# noodle.net
KiCad netlist of a schematic drawn in EAGLE
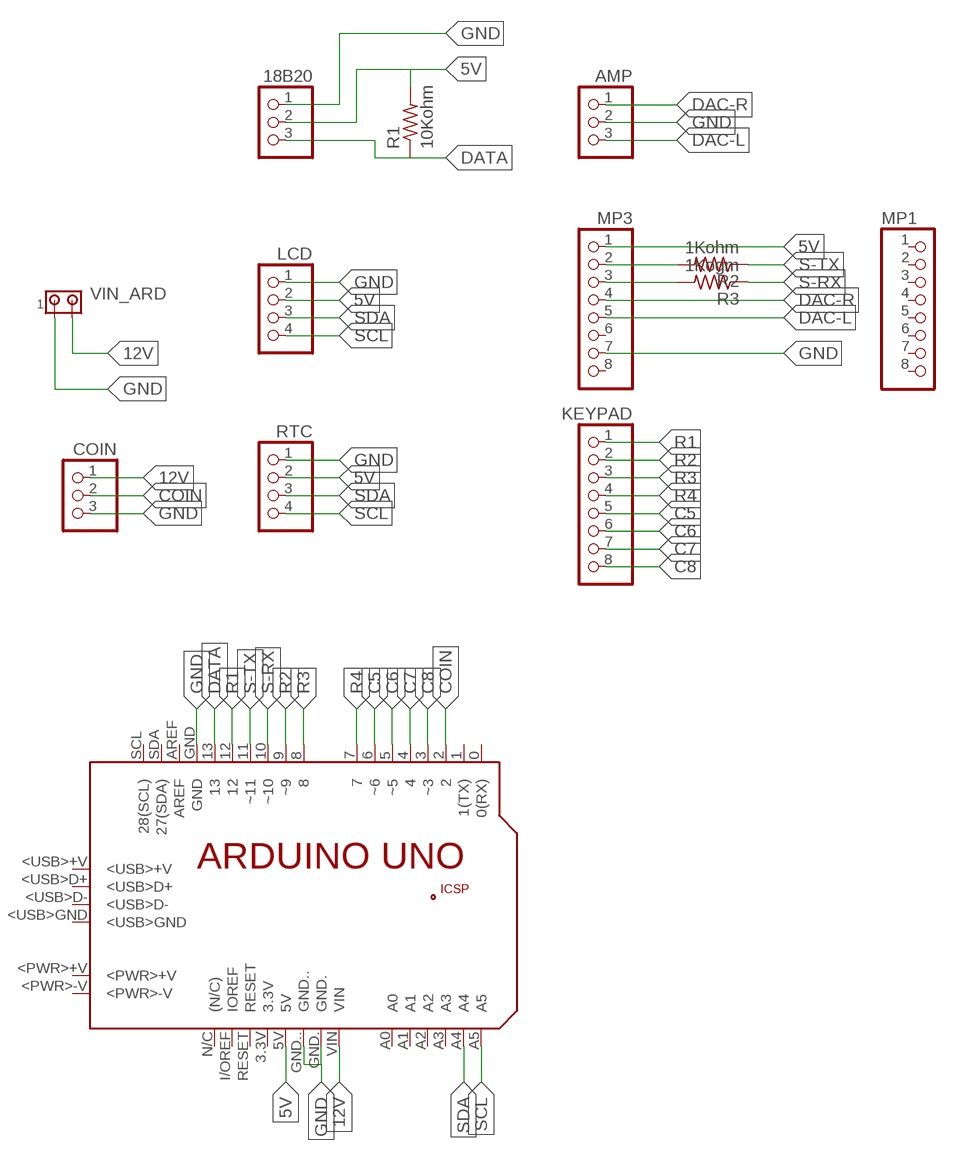
[diagram p0: schematic, sheet 1]

(export (version "E")
  (design (tool "Eeschema 10.0.6"))
  (components
    (comp (ref "18B20")
      (value "PINHD-1X3")
      (footprint "eagle-import:1X03")
      (libsource (lib "eagle-import") (part "PINHD-1X3"))
    )
    (comp (ref "AMP")
      (value "PINHD-1X3")
      (footprint "eagle-import:1X03")
      (libsource (lib "eagle-import") (part "PINHD-1X3"))
    )
    (comp (ref "COIN")
      (value "PINHD-1X3")
      (footprint "eagle-import:1X03")
      (libsource (lib "eagle-import") (part "PINHD-1X3"))
    )
    (comp (ref "KEYPAD")
      (value "PINHD-1X8")
      (footprint "eagle-import:1X08")
      (libsource (lib "eagle-import") (part "PINHD-1X8"))
    )
    (comp (ref "LCD")
      (value "PINHD-1X4")
      (footprint "eagle-import:1X04")
      (libsource (lib "eagle-import") (part "PINHD-1X4"))
    )
    (comp (ref "MP1")
      (value "PINHD-1X8")
      (footprint "eagle-import:1X08")
      (libsource (lib "eagle-import") (part "PINHD-1X8"))
    )
    (comp (ref "MP3")
      (value "PINHD-1X8")
      (footprint "eagle-import:1X08")
      (libsource (lib "eagle-import") (part "PINHD-1X8"))
    )
    (comp (ref "PCB1")
      (value "ARDUINO_UNO")
      (footprint "eagle-import:ARDUINO_UNO")
      (libsource (lib "eagle-import") (part "ARDUINO_UNO"))
    )
    (comp (ref "R1")
      (value "10Kohm")
      (footprint "eagle-import:0207_10")
      (libsource (lib "eagle-import") (part "R-US_0207/10"))
    )
    (comp (ref "R2")
      (value "1Kohm")
      (footprint "eagle-import:0207_10")
      (libsource (lib "eagle-import") (part "R-US_0207/10"))
    )
    (comp (ref "R3")
      (value "1Kogm")
      (footprint "eagle-import:0207_10")
      (libsource (lib "eagle-import") (part "R-US_0207/10"))
    )
    (comp (ref "RTC")
      (value "PINHD-1X4")
      (footprint "eagle-import:1X04")
      (libsource (lib "eagle-import") (part "PINHD-1X4"))
    )
    (comp (ref "VIN_ARD")
      (value "MTA02-156")
      (footprint "eagle-import:1X2MTA")
      (libsource (lib "eagle-import") (part "MTA02-156"))
    )
  )
  (nets
    (net (code "1") (name "5V") (class "Default")
      (node (ref "18B20") (pin "2") (pinfunction "2_2") (pintype "passive"))
      (node (ref "LCD") (pin "2") (pinfunction "2_2") (pintype "passive"))
      (node (ref "MP3") (pin "1") (pinfunction "1_1") (pintype "passive"))
      (node (ref "PCB1") (pin "5V") (pinfunction "5V_5V") (pintype "bidirectional"))
      (node (ref "R1") (pin "2") (pinfunction "2_2") (pintype "passive"))
      (node (ref "RTC") (pin "2") (pinfunction "2_2") (pintype "passive"))
    )
    (net (code "2") (name "12V") (class "Default")
      (node (ref "COIN") (pin "1") (pinfunction "1_1") (pintype "passive"))
      (node (ref "PCB1") (pin "VIN") (pinfunction "VIN_VIN") (pintype "bidirectional"))
      (node (ref "VIN_ARD") (pin "2") (pinfunction "2_2") (pintype "passive"))
    )
    (net (code "3") (name "C5") (class "Default")
      (node (ref "KEYPAD") (pin "5") (pinfunction "5_5") (pintype "passive"))
      (node (ref "PCB1") (pin "6") (pinfunction "~{6}_6") (pintype "bidirectional"))
    )
    (net (code "4") (name "C6") (class "Default")
      (node (ref "KEYPAD") (pin "6") (pinfunction "6_6") (pintype "passive"))
      (node (ref "PCB1") (pin "5") (pinfunction "~{5}_5") (pintype "bidirectional"))
    )
    (net (code "5") (name "C7") (class "Default")
      (node (ref "KEYPAD") (pin "7") (pinfunction "7_7") (pintype "passive"))
      (node (ref "PCB1") (pin "4") (pinfunction "4_4") (pintype "bidirectional"))
    )
    (net (code "6") (name "C8") (class "Default")
      (node (ref "KEYPAD") (pin "8") (pinfunction "8_8") (pintype "passive"))
      (node (ref "PCB1") (pin "3") (pinfunction "~{3}_3") (pintype "bidirectional"))
    )
    (net (code "7") (name "COIN") (class "Default")
      (node (ref "COIN") (pin "2") (pinfunction "2_2") (pintype "passive"))
      (node (ref "PCB1") (pin "2") (pinfunction "2_2") (pintype "bidirectional"))
    )
    (net (code "8") (name "DAC-L") (class "Default")
      (node (ref "AMP") (pin "3") (pinfunction "3_3") (pintype "passive"))
      (node (ref "MP3") (pin "5") (pinfunction "5_5") (pintype "passive"))
    )
    (net (code "9") (name "DAC-R") (class "Default")
      (node (ref "AMP") (pin "1") (pinfunction "1_1") (pintype "passive"))
      (node (ref "MP3") (pin "4") (pinfunction "4_4") (pintype "passive"))
    )
    (net (code "10") (name "DATA") (class "Default")
      (node (ref "18B20") (pin "3") (pinfunction "3_3") (pintype "passive"))
      (node (ref "PCB1") (pin "13") (pinfunction "13_13") (pintype "bidirectional"))
      (node (ref "R1") (pin "1") (pinfunction "1_1") (pintype "passive"))
    )
    (net (code "11") (name "GND") (class "Default")
      (node (ref "18B20") (pin "1") (pinfunction "1_1") (pintype "passive"))
      (node (ref "AMP") (pin "2") (pinfunction "2_2") (pintype "passive"))
      (node (ref "COIN") (pin "3") (pinfunction "3_3") (pintype "passive"))
      (node (ref "LCD") (pin "1") (pinfunction "1_1") (pintype "passive"))
      (node (ref "MP3") (pin "7") (pinfunction "7_7") (pintype "passive"))
      (node (ref "PCB1") (pin "GND") (pinfunction "GND_GND") (pintype "bidirectional"))
      (node (ref "PCB1") (pin "GND.") (pinfunction "GND._GND.") (pintype "bidirectional"))
      (node (ref "PCB1") (pin "GND..") (pinfunction "GND.._GND..") (pintype "bidirectional"))
      (node (ref "RTC") (pin "1") (pinfunction "1_1") (pintype "passive"))
      (node (ref "VIN_ARD") (pin "1") (pinfunction "1_1") (pintype "passive"))
    )
    (net (code "12") (name "Net-(MP3-Pad2)") (class "Default")
      (node (ref "MP3") (pin "2") (pinfunction "2_2") (pintype "passive"))
      (node (ref "R2") (pin "2") (pinfunction "2_2") (pintype "passive"))
    )
    (net (code "13") (name "Net-(MP3-Pad3)") (class "Default")
      (node (ref "MP3") (pin "3") (pinfunction "3_3") (pintype "passive"))
      (node (ref "R3") (pin "2") (pinfunction "2_2") (pintype "passive"))
    )
    (net (code "14") (name "R1") (class "Default")
      (node (ref "KEYPAD") (pin "1") (pinfunction "1_1") (pintype "passive"))
      (node (ref "PCB1") (pin "12") (pinfunction "12_12") (pintype "bidirectional"))
    )
    (net (code "15") (name "R2") (class "Default")
      (node (ref "KEYPAD") (pin "2") (pinfunction "2_2") (pintype "passive"))
      (node (ref "PCB1") (pin "9") (pinfunction "~{9}_9") (pintype "bidirectional"))
    )
    (net (code "16") (name "R3") (class "Default")
      (node (ref "KEYPAD") (pin "3") (pinfunction "3_3") (pintype "passive"))
      (node (ref "PCB1") (pin "8") (pinfunction "8_8") (pintype "bidirectional"))
    )
    (net (code "17") (name "R4") (class "Default")
      (node (ref "KEYPAD") (pin "4") (pinfunction "4_4") (pintype "passive"))
      (node (ref "PCB1") (pin "7") (pinfunction "7_7") (pintype "bidirectional"))
    )
    (net (code "18") (name "S-RX") (class "Default")
      (node (ref "PCB1") (pin "10") (pinfunction "~{10}_10") (pintype "bidirectional"))
      (node (ref "R3") (pin "1") (pinfunction "1_1") (pintype "passive"))
    )
    (net (code "19") (name "S-TX") (class "Default")
      (node (ref "PCB1") (pin "11") (pinfunction "~{11}_11") (pintype "bidirectional"))
      (node (ref "R2") (pin "1") (pinfunction "1_1") (pintype "passive"))
    )
    (net (code "20") (name "SCL") (class "Default")
      (node (ref "LCD") (pin "4") (pinfunction "4_4") (pintype "passive"))
      (node (ref "PCB1") (pin "A5") (pinfunction "A5_A5") (pintype "bidirectional"))
      (node (ref "RTC") (pin "4") (pinfunction "4_4") (pintype "passive"))
    )
    (net (code "21") (name "SDA") (class "Default")
      (node (ref "LCD") (pin "3") (pinfunction "3_3") (pintype "passive"))
      (node (ref "PCB1") (pin "A4") (pinfunction "A4_A4") (pintype "bidirectional"))
      (node (ref "RTC") (pin "3") (pinfunction "3_3") (pintype "passive"))
    )
    (net (code "22") (name "unconnected-(MP1-Pad1)") (class "Default")
      (node (ref "MP1") (pin "1") (pinfunction "1_1") (pintype "passive"))
    )
    (net (code "23") (name "unconnected-(MP1-Pad2)") (class "Default")
      (node (ref "MP1") (pin "2") (pinfunction "2_2") (pintype "passive"))
    )
    (net (code "24") (name "unconnected-(MP1-Pad3)") (class "Default")
      (node (ref "MP1") (pin "3") (pinfunction "3_3") (pintype "passive"))
    )
    (net (code "25") (name "unconnected-(MP1-Pad4)") (class "Default")
      (node (ref "MP1") (pin "4") (pinfunction "4_4") (pintype "passive"))
    )
    (net (code "26") (name "unconnected-(MP1-Pad5)") (class "Default")
      (node (ref "MP1") (pin "5") (pinfunction "5_5") (pintype "passive"))
    )
    (net (code "27") (name "unconnected-(MP1-Pad6)") (class "Default")
      (node (ref "MP1") (pin "6") (pinfunction "6_6") (pintype "passive"))
    )
    (net (code "28") (name "unconnected-(MP1-Pad7)") (class "Default")
      (node (ref "MP1") (pin "7") (pinfunction "7_7") (pintype "passive"))
    )
    (net (code "29") (name "unconnected-(MP1-Pad8)") (class "Default")
      (node (ref "MP1") (pin "8") (pinfunction "8_8") (pintype "passive"))
    )
    (net (code "30") (name "unconnected-(MP3-Pad6)") (class "Default")
      (node (ref "MP3") (pin "6") (pinfunction "6_6") (pintype "passive"))
    )
    (net (code "31") (name "unconnected-(MP3-Pad8)") (class "Default")
      (node (ref "MP3") (pin "8") (pinfunction "8_8") (pintype "passive"))
    )
    (net (code "32") (name "unconnected-(PCB1-(N{slash}C)-PadN{slash}C)") (class "Default")
      (node (ref "PCB1") (pin "N/C") (pinfunction "(N/C)_N/C") (pintype "bidirectional"))
    )
    (net (code "33") (name "unconnected-(PCB1-0(RX)-Pad0)") (class "Default")
      (node (ref "PCB1") (pin "0") (pinfunction "0(RX)_0") (pintype "bidirectional"))
    )
    (net (code "34") (name "unconnected-(PCB1-1(TX)-Pad1)") (class "Default")
      (node (ref "PCB1") (pin "1") (pinfunction "1(TX)_1") (pintype "bidirectional"))
    )
    (net (code "35") (name "unconnected-(PCB1-27(SDA)-PadSDA)") (class "Default")
      (node (ref "PCB1") (pin "SDA") (pinfunction "27(SDA)_SDA") (pintype "bidirectional"))
    )
    (net (code "36") (name "unconnected-(PCB1-28(SCL)-PadSCL)") (class "Default")
      (node (ref "PCB1") (pin "SCL") (pinfunction "28(SCL)_SCL") (pintype "bidirectional"))
    )
    (net (code "37") (name "unconnected-(PCB1-IOREF-PadI{slash}OREF)") (class "Default")
      (node (ref "PCB1") (pin "I/OREF") (pinfunction "IOREF_I/OREF") (pintype "bidirectional"))
    )
    (net (code "38") (name "unconnected-(PCB1-Pad+5V)") (class "Default")
      (node (ref "PCB1") (pin "+5V") (pinfunction "+5V_+5V") (pintype "bidirectional"))
    )
    (net (code "39") (name "unconnected-(PCB1-Pad3.3V)") (class "Default")
      (node (ref "PCB1") (pin "3.3V") (pinfunction "3.3V_3.3V") (pintype "bidirectional"))
    )
    (net (code "40") (name "unconnected-(PCB1-Pad<PWR>+V)") (class "Default")
      (node (ref "PCB1") (pin "<PWR>+V") (pinfunction "<PWR>+V_<PWR>+V") (pintype "bidirectional"))
    )
    (net (code "41") (name "unconnected-(PCB1-Pad<PWR>-V)") (class "Default")
      (node (ref "PCB1") (pin "<PWR>-V") (pinfunction "<PWR>-V_<PWR>-V") (pintype "bidirectional"))
    )
    (net (code "42") (name "unconnected-(PCB1-Pad<USB>+V)") (class "Default")
      (node (ref "PCB1") (pin "<USB>+V") (pinfunction "<USB>+V_<USB>+V") (pintype "bidirectional"))
    )
    (net (code "43") (name "unconnected-(PCB1-Pad<USB>D+)") (class "Default")
      (node (ref "PCB1") (pin "<USB>D+") (pinfunction "<USB>D+_<USB>D+") (pintype "bidirectional"))
    )
    (net (code "44") (name "unconnected-(PCB1-Pad<USB>D-)") (class "Default")
      (node (ref "PCB1") (pin "<USB>D-") (pinfunction "<USB>D-_<USB>D-") (pintype "bidirectional"))
    )
    (net (code "45") (name "unconnected-(PCB1-Pad<USB>GND)") (class "Default")
      (node (ref "PCB1") (pin "<USB>GND") (pinfunction "<USB>GND_<USB>GND") (pintype "bidirectional"))
    )
    (net (code "46") (name "unconnected-(PCB1-PadA0)") (class "Default")
      (node (ref "PCB1") (pin "A0") (pinfunction "A0_A0") (pintype "bidirectional"))
    )
    (net (code "47") (name "unconnected-(PCB1-PadA1)") (class "Default")
      (node (ref "PCB1") (pin "A1") (pinfunction "A1_A1") (pintype "bidirectional"))
    )
    (net (code "48") (name "unconnected-(PCB1-PadA2)") (class "Default")
      (node (ref "PCB1") (pin "A2") (pinfunction "A2_A2") (pintype "bidirectional"))
    )
    (net (code "49") (name "unconnected-(PCB1-PadA3)") (class "Default")
      (node (ref "PCB1") (pin "A3") (pinfunction "A3_A3") (pintype "bidirectional"))
    )
    (net (code "50") (name "unconnected-(PCB1-PadAREF)") (class "Default")
      (node (ref "PCB1") (pin "AREF") (pinfunction "AREF_AREF") (pintype "bidirectional"))
    )
    (net (code "51") (name "unconnected-(PCB1-PadGND_)") (class "Default")
      (node (ref "PCB1") (pin "GND_") (pinfunction "GND__GND_") (pintype "bidirectional"))
    )
    (net (code "52") (name "unconnected-(PCB1-PadMISO)") (class "Default")
      (node (ref "PCB1") (pin "MISO") (pinfunction "MISO_MISO") (pintype "bidirectional"))
    )
    (net (code "53") (name "unconnected-(PCB1-PadMOSI)") (class "Default")
      (node (ref "PCB1") (pin "MOSI") (pinfunction "MOSI_MOSI") (pintype "bidirectional"))
    )
    (net (code "54") (name "unconnected-(PCB1-PadRESET)") (class "Default")
      (node (ref "PCB1") (pin "RESET") (pinfunction "RESET_RESET") (pintype "bidirectional"))
    )
    (net (code "55") (name "unconnected-(PCB1-PadRESET.)") (class "Default")
      (node (ref "PCB1") (pin "RESET.") (pinfunction "RESET._RESET.") (pintype "bidirectional"))
    )
    (net (code "56") (name "unconnected-(PCB1-PadSCK)") (class "Default")
      (node (ref "PCB1") (pin "SCK") (pinfunction "SCK_SCK") (pintype "bidirectional"))
    )
  )
)
